# TTFT_LIS2DS12.net
KiCad netlist of a schematic drawn in Altium Designer
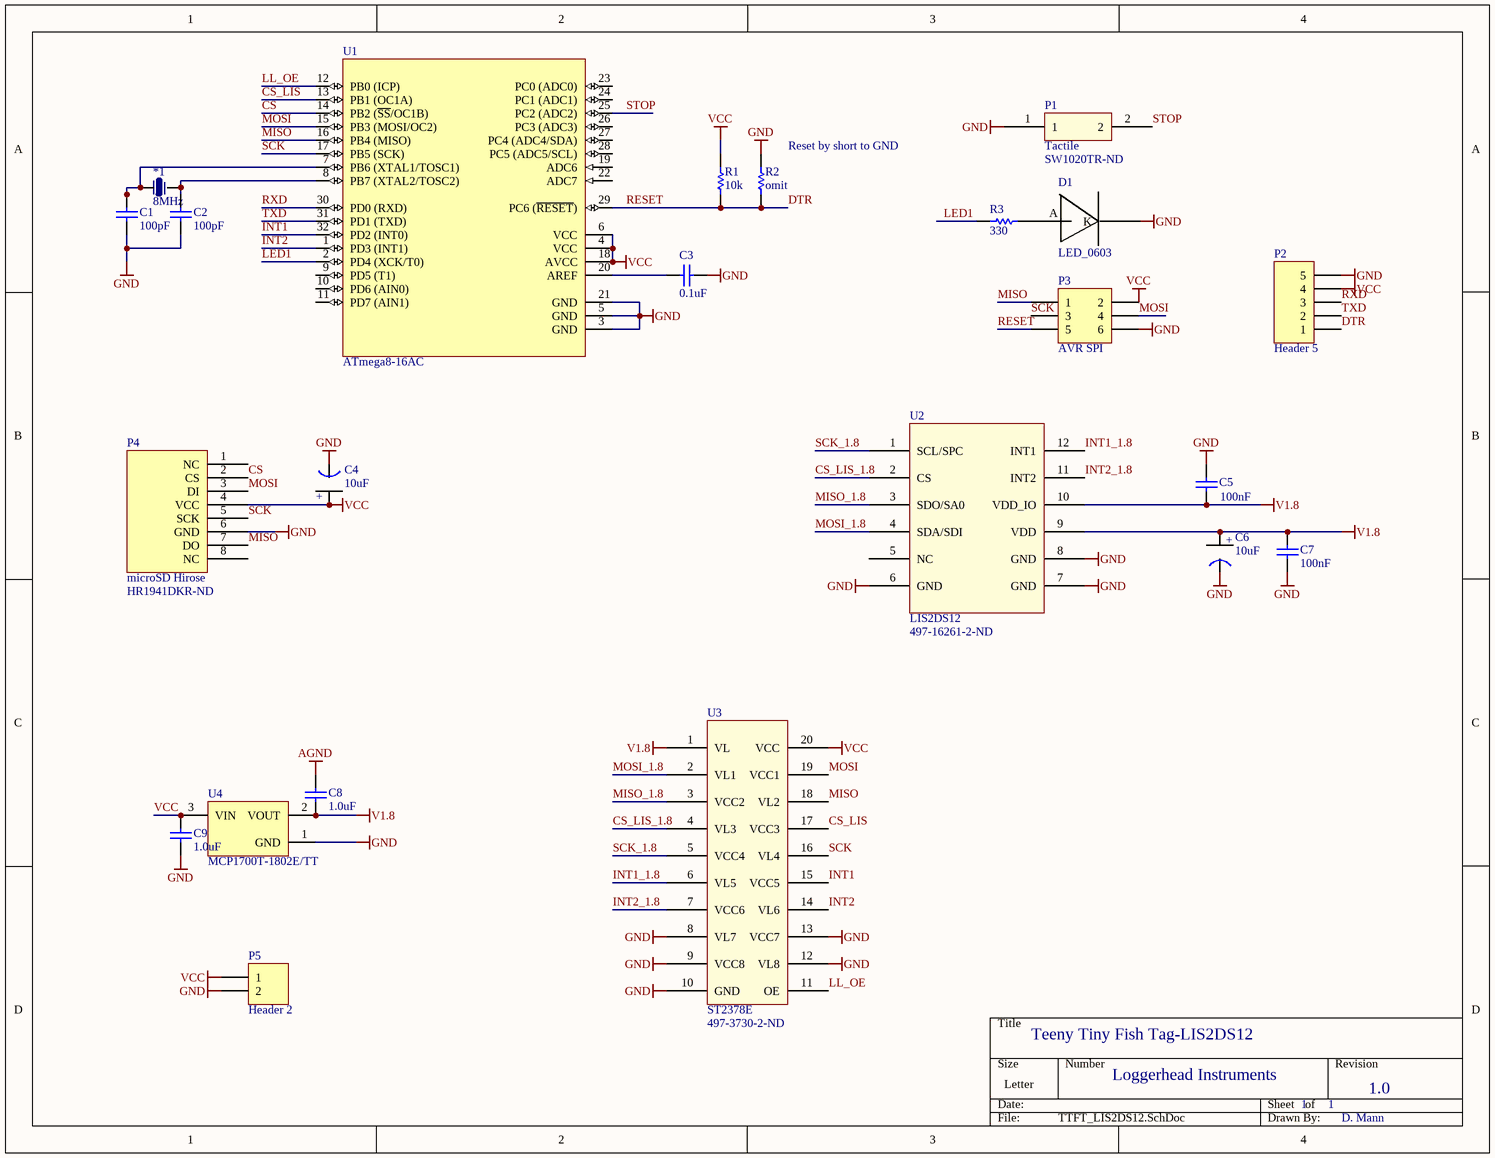
[diagram p0: TTFT_LIS2DS12.SchDoc]

(export (version "E")
  (design (tool "Eeschema 10.0.6"))
  (components
    (comp (ref "*1") (value "8MHz") (footprint "XTAL-ABM3") (libsource (lib "Loggerhead") (part "XTAL-ABM3")))
    (comp (ref "C1")
      (value "100pF")
      (footprint "0402")
      (description "Ceramic Chip Capacitor - Standard")
      (fields (field (name "PUBLISHER") "Altium Limited"))
      (libsource (lib "KEMET Chip Capacitor") (part "C0402"))
    )
    (comp (ref "C2")
      (value "100pF")
      (footprint "0402")
      (description "Ceramic Chip Capacitor - Standard")
      (fields (field (name "PUBLISHER") "Altium Limited"))
      (libsource (lib "KEMET Chip Capacitor") (part "C0402"))
    )
    (comp (ref "C3")
      (value "0.1uF")
      (footprint "0402")
      (description "Ceramic Chip Capacitor - Standard")
      (fields (field (name "PUBLISHER") "Altium Limited"))
      (libsource (lib "KEMET Chip Capacitor") (part "C0402"))
    )
    (comp (ref "C4") (value "10uF") (footprint "Tant0805") (libsource (lib "Loggerhead") (part "Tant0805")))
    (comp (ref "C5")
      (value "100nF")
      (footprint "0402")
      (description "Ceramic Chip Capacitor - Standard")
      (fields (field (name "PUBLISHER") "Altium Limited"))
      (libsource (lib "KEMET Chip Capacitor") (part "C0402"))
    )
    (comp (ref "C6") (value "10uF") (footprint "Tant0805") (libsource (lib "Loggerhead") (part "Tant0805")))
    (comp (ref "C7")
      (value "100nF")
      (footprint "0402")
      (description "Ceramic Chip Capacitor - Standard")
      (fields (field (name "PUBLISHER") "Altium Limited"))
      (libsource (lib "KEMET Chip Capacitor") (part "C0402"))
    )
    (comp (ref "C8")
      (value "1.0uF")
      (footprint "0402")
      (description "Ceramic Chip Capacitor - Standard")
      (fields (field (name "PUBLISHER") "Altium Limited"))
      (libsource (lib "KEMET Chip Capacitor") (part "C0402"))
    )
    (comp (ref "C9")
      (value "1.0uF")
      (footprint "0402")
      (description "Ceramic Chip Capacitor - Standard")
      (fields (field (name "PUBLISHER") "Altium Limited"))
      (libsource (lib "KEMET Chip Capacitor") (part "C0402"))
    )
    (comp (ref "D1")
      (value "LED_0603")
      (footprint "Diode0603")
      (libsource (lib "Loggerhead") (part "LED_0603"))
    )
    (comp (ref "P1")
      (value "Tactile")
      (footprint "Tactile-B3U-1000")
      (fields (field (name "SUPPLIER PART NUMBER 1") "SW1020TR-ND"))
      (libsource (lib "Loggerhead") (part "Tactile_B3U-1000"))
    )
    (comp (ref "P2")
      (value "Header 5")
      (footprint "HDR1X5")
      (description "Header, 5-Pin")
      (fields (field (name "PUBLISHER") "Altium Limited"))
      (libsource (lib "Miscellaneous Connectors") (part "Header 5"))
    )
    (comp (ref "P3")
      (value "AVR SPI")
      (footprint "HDR2X3")
      (description "Header, 3-Pin, Dual row")
      (fields (field (name "PUBLISHER") "Altium Limited"))
      (libsource (lib "Miscellaneous Connectors") (part "Header 3X2"))
    )
    (comp (ref "P4")
      (value "microSD Hirose")
      (footprint "DM3D microSD")
      (fields (field (name "SUPPLIER PART NUMBER 1") "HR1941DKR-ND"))
      (libsource (lib "Loggerhead") (part "microSD Hirose"))
    )
    (comp (ref "P5")
      (value "Header 2")
      (footprint "HDR1X2")
      (description "Header, 2-Pin")
      (fields (field (name "PUBLISHER") "Altium Limited"))
      (libsource (lib "Miscellaneous Connectors") (part "Header 2"))
    )
    (comp (ref "R1")
      (value "10k")
      (footprint "3-0603")
      (fields (field (name "PUBLISHER") "Altium Limited"))
      (libsource (lib "Panasonic Resistor") (part "ERJ3RK"))
    )
    (comp (ref "R2")
      (value "omit")
      (footprint "3-0603")
      (fields (field (name "PUBLISHER") "Altium Limited"))
      (libsource (lib "Panasonic Resistor") (part "ERJ3RK"))
    )
    (comp (ref "R3")
      (value "330")
      (footprint "3-0603")
      (fields (field (name "PUBLISHER") "Altium Limited"))
      (libsource (lib "Panasonic Resistor") (part "ERJ3RK"))
    )
    (comp (ref "U1")
      (value "ATmega8-16AC")
      (footprint "32M1-A_M")
      (description "8-Bit AVR Microcontroller with 8K Bytes of In-System Programmable Flash Memory")
      (fields (field (name "PUBLISHER") "Altium Limited"))
      (libsource (lib "Atmel Microcontroller 8-Bit AVR") (part "ATmega8-16AC"))
    )
    (comp (ref "U2")
      (value "LIS2DS12")
      (footprint "LGA-12")
      (fields (field (name "SUPPLIER PART NUMBER 1") "497-16261-2-ND"))
      (libsource (lib "Loggerhead") (part "LIS2DS12"))
    )
    (comp (ref "U3")
      (value "ST2378E")
      (footprint "TSSOP20")
      (fields (field (name "SUPPLIER PART NUMBER 1") "497-3730-2-ND"))
      (libsource (lib "Loggerhead") (part "ST2378E"))
    )
    (comp (ref "U4")
      (value "MCP1700T-1802E/TT")
      (footprint "SOT-23-TT3_N")
      (description "Low Quiescent Current LDO, 3-Pin SOT-23, Extended Temperature, Tape and Reel")
      (fields (field (name "MANUFACTURER") "Microchip"))
      (libsource (lib "Microchip Power Management Line Regulator") (part "MCP1700T-1802E/TT"))
    )
  )
  (nets
    (net (code "1") (name "/CS") (class "Default")
      (node (ref "P4") (pin "2") (pinfunction "CS_2") (pintype "passive"))
      (node (ref "U1") (pin "14") (pinfunction "PB2_(~{SS}/OC1B)_14") (pintype "bidirectional"))
    )
    (net (code "2") (name "/CS_LIS") (class "Default")
      (node (ref "U1") (pin "13") (pinfunction "PB1_(OC1A)_13") (pintype "bidirectional"))
      (node (ref "U3") (pin "17") (pinfunction "VCC3_17") (pintype "passive"))
    )
    (net (code "3") (name "/CS_LIS_1.8") (class "Default")
      (node (ref "U2") (pin "2") (pinfunction "CS_2") (pintype "passive"))
      (node (ref "U3") (pin "4") (pinfunction "VL3_4") (pintype "passive"))
    )
    (net (code "4") (name "/DTR") (class "Default")
      (node (ref "P2") (pin "1") (pinfunction "1_1") (pintype "passive"))
      (node (ref "P3") (pin "5") (pinfunction "5_5") (pintype "passive"))
      (node (ref "R1") (pin "1") (pinfunction "1_1") (pintype "passive"))
      (node (ref "R2") (pin "1") (pinfunction "1_1") (pintype "passive"))
      (node (ref "U1") (pin "29") (pinfunction "PC6_(~{RESET})_29") (pintype "bidirectional"))
    )
    (net (code "5") (name "/INT1") (class "Default")
      (node (ref "U1") (pin "32") (pinfunction "PD2_(INT0)_32") (pintype "bidirectional"))
      (node (ref "U3") (pin "15") (pinfunction "VCC5_15") (pintype "passive"))
    )
    (net (code "6") (name "/INT1_1.8") (class "Default")
      (node (ref "U2") (pin "12") (pinfunction "INT1_12") (pintype "passive"))
      (node (ref "U3") (pin "6") (pinfunction "VL5_6") (pintype "passive"))
    )
    (net (code "7") (name "/INT2") (class "Default")
      (node (ref "U1") (pin "1") (pinfunction "PD3_(INT1)_1") (pintype "bidirectional"))
      (node (ref "U3") (pin "14") (pinfunction "VL6_14") (pintype "passive"))
    )
    (net (code "8") (name "/INT2_1.8") (class "Default")
      (node (ref "U2") (pin "11") (pinfunction "INT2_11") (pintype "passive"))
      (node (ref "U3") (pin "7") (pinfunction "VCC6_7") (pintype "passive"))
    )
    (net (code "9") (name "/LED1") (class "Default")
      (node (ref "R3") (pin "1") (pinfunction "1_1") (pintype "passive"))
      (node (ref "U1") (pin "2") (pinfunction "PD4_(XCK/T0)_2") (pintype "bidirectional"))
    )
    (net (code "10") (name "/LL_OE") (class "Default")
      (node (ref "U1") (pin "12") (pinfunction "PB0_(ICP)_12") (pintype "bidirectional"))
      (node (ref "U3") (pin "11") (pinfunction "OE_11") (pintype "passive"))
    )
    (net (code "11") (name "/MISO") (class "Default")
      (node (ref "P3") (pin "1") (pinfunction "1_1") (pintype "passive"))
      (node (ref "P4") (pin "7") (pinfunction "DO_7") (pintype "passive"))
      (node (ref "U1") (pin "16") (pinfunction "PB4_(MISO)_16") (pintype "bidirectional"))
      (node (ref "U3") (pin "18") (pinfunction "VL2_18") (pintype "passive"))
    )
    (net (code "12") (name "/MISO_1.8") (class "Default")
      (node (ref "U2") (pin "3") (pinfunction "SDO/SA0_3") (pintype "passive"))
      (node (ref "U3") (pin "3") (pinfunction "VCC2_3") (pintype "passive"))
    )
    (net (code "13") (name "/MOSI") (class "Default")
      (node (ref "P3") (pin "4") (pinfunction "4_4") (pintype "passive"))
      (node (ref "P4") (pin "3") (pinfunction "DI_3") (pintype "passive"))
      (node (ref "U1") (pin "15") (pinfunction "PB3_(MOSI/OC2)_15") (pintype "bidirectional"))
      (node (ref "U3") (pin "19") (pinfunction "VCC1_19") (pintype "passive"))
    )
    (net (code "14") (name "/MOSI_1.8") (class "Default")
      (node (ref "U2") (pin "4") (pinfunction "SDA/SDI_4") (pintype "passive"))
      (node (ref "U3") (pin "2") (pinfunction "VL1_2") (pintype "passive"))
    )
    (net (code "15") (name "/RXD") (class "Default")
      (node (ref "P2") (pin "3") (pinfunction "3_3") (pintype "passive"))
      (node (ref "U1") (pin "30") (pinfunction "PD0_(RXD)_30") (pintype "bidirectional"))
    )
    (net (code "16") (name "/SCK") (class "Default")
      (node (ref "P3") (pin "3") (pinfunction "3_3") (pintype "passive"))
      (node (ref "P4") (pin "5") (pinfunction "SCK_5") (pintype "passive"))
      (node (ref "U1") (pin "17") (pinfunction "PB5_(SCK)_17") (pintype "bidirectional"))
      (node (ref "U3") (pin "16") (pinfunction "VL4_16") (pintype "passive"))
    )
    (net (code "17") (name "/SCK_1.8") (class "Default")
      (node (ref "U2") (pin "1") (pinfunction "SCL/SPC_1") (pintype "passive"))
      (node (ref "U3") (pin "5") (pinfunction "VCC4_5") (pintype "passive"))
    )
    (net (code "18") (name "/STOP") (class "Default")
      (node (ref "P1") (pin "2") (pinfunction "2_2") (pintype "passive"))
      (node (ref "U1") (pin "25") (pinfunction "PC2_(ADC2)_25") (pintype "bidirectional"))
    )
    (net (code "19") (name "/TXD") (class "Default")
      (node (ref "P2") (pin "2") (pinfunction "2_2") (pintype "passive"))
      (node (ref "U1") (pin "31") (pinfunction "PD1_(TXD)_31") (pintype "bidirectional"))
    )
    (net (code "20") (name "AGND") (class "Default")
      (node (ref "C8") (pin "2") (pinfunction "2_2") (pintype "passive"))
    )
    (net (code "21") (name "GND") (class "Default")
      (node (ref "C1") (pin "1") (pinfunction "1_1") (pintype "passive"))
      (node (ref "C2") (pin "1") (pinfunction "1_1") (pintype "passive"))
      (node (ref "C3") (pin "2") (pinfunction "2_2") (pintype "passive"))
      (node (ref "C4") (pin "1") (pinfunction "GND_1") (pintype "passive"))
      (node (ref "C5") (pin "2") (pinfunction "2_2") (pintype "passive"))
      (node (ref "C6") (pin "1") (pinfunction "GND_1") (pintype "passive"))
      (node (ref "C7") (pin "2") (pinfunction "2_2") (pintype "passive"))
      (node (ref "C9") (pin "2") (pinfunction "2_2") (pintype "passive"))
      (node (ref "D1") (pin "K") (pinfunction "K_K") (pintype "passive"))
      (node (ref "P1") (pin "1") (pinfunction "1_1") (pintype "passive"))
      (node (ref "P2") (pin "5") (pinfunction "5_5") (pintype "passive"))
      (node (ref "P3") (pin "6") (pinfunction "6_6") (pintype "passive"))
      (node (ref "P4") (pin "6") (pinfunction "GND_6") (pintype "passive"))
      (node (ref "P5") (pin "2") (pinfunction "2_2") (pintype "passive"))
      (node (ref "R2") (pin "2") (pinfunction "2_2") (pintype "passive"))
      (node (ref "U1") (pin "21") (pinfunction "GND_21") (pintype "power_in"))
      (node (ref "U1") (pin "3") (pinfunction "GND_3") (pintype "power_in"))
      (node (ref "U1") (pin "5") (pinfunction "GND_5") (pintype "power_in"))
      (node (ref "U2") (pin "6") (pinfunction "GND_6") (pintype "passive"))
      (node (ref "U2") (pin "7") (pinfunction "GND_7") (pintype "passive"))
      (node (ref "U2") (pin "8") (pinfunction "GND_8") (pintype "passive"))
      (node (ref "U3") (pin "10") (pinfunction "GND_10") (pintype "passive"))
      (node (ref "U3") (pin "12") (pinfunction "VL8_12") (pintype "passive"))
      (node (ref "U3") (pin "13") (pinfunction "VCC7_13") (pintype "passive"))
      (node (ref "U3") (pin "8") (pinfunction "VL7_8") (pintype "passive"))
      (node (ref "U3") (pin "9") (pinfunction "VCC8_9") (pintype "passive"))
      (node (ref "U4") (pin "1") (pinfunction "GND_1") (pintype "power_in"))
    )
    (net (code "22") (name "Net-(D1-PadA)") (class "Default")
      (node (ref "D1") (pin "A") (pinfunction "A_A") (pintype "passive"))
      (node (ref "R3") (pin "2") (pinfunction "2_2") (pintype "passive"))
    )
    (net (code "23") (name "Net-(U1-AREF)") (class "Default")
      (node (ref "C3") (pin "1") (pinfunction "1_1") (pintype "passive"))
      (node (ref "U1") (pin "20") (pinfunction "AREF_20") (pintype "passive"))
    )
    (net (code "24") (name "Net-(U1-PB6_(XTAL1{slash}TOSC1))") (class "Default")
      (node (ref "*1") (pin "1") (pinfunction "1_1") (pintype "passive"))
      (node (ref "C1") (pin "2") (pinfunction "2_2") (pintype "passive"))
      (node (ref "U1") (pin "7") (pinfunction "PB6_(XTAL1/TOSC1)_7") (pintype "bidirectional"))
    )
    (net (code "25") (name "Net-(U1-PB7_(XTAL2{slash}TOSC2))") (class "Default")
      (node (ref "*1") (pin "2") (pinfunction "2_2") (pintype "passive"))
      (node (ref "C2") (pin "2") (pinfunction "2_2") (pintype "passive"))
      (node (ref "U1") (pin "8") (pinfunction "PB7_(XTAL2/TOSC2)_8") (pintype "bidirectional"))
    )
    (net (code "26") (name "V1.8") (class "Default")
      (node (ref "C5") (pin "1") (pinfunction "1_1") (pintype "passive"))
      (node (ref "C6") (pin "2") (pinfunction "+_2") (pintype "passive"))
      (node (ref "C7") (pin "1") (pinfunction "1_1") (pintype "passive"))
      (node (ref "C8") (pin "1") (pinfunction "1_1") (pintype "passive"))
      (node (ref "U2") (pin "10") (pinfunction "VDD_IO_10") (pintype "passive"))
      (node (ref "U2") (pin "9") (pinfunction "VDD_9") (pintype "passive"))
      (node (ref "U3") (pin "1") (pinfunction "VL_1") (pintype "passive"))
      (node (ref "U4") (pin "2") (pinfunction "VOUT_2") (pintype "power_in"))
    )
    (net (code "27") (name "VCC") (class "Default")
      (node (ref "C4") (pin "2") (pinfunction "+_2") (pintype "passive"))
      (node (ref "C9") (pin "1") (pinfunction "1_1") (pintype "passive"))
      (node (ref "P2") (pin "4") (pinfunction "4_4") (pintype "passive"))
      (node (ref "P3") (pin "2") (pinfunction "2_2") (pintype "passive"))
      (node (ref "P4") (pin "4") (pinfunction "VCC_4") (pintype "passive"))
      (node (ref "P5") (pin "1") (pinfunction "1_1") (pintype "passive"))
      (node (ref "R1") (pin "2") (pinfunction "2_2") (pintype "passive"))
      (node (ref "U1") (pin "18") (pinfunction "AVCC_18") (pintype "power_in"))
      (node (ref "U1") (pin "4") (pinfunction "VCC_4") (pintype "power_in"))
      (node (ref "U1") (pin "6") (pinfunction "VCC_6") (pintype "power_in"))
      (node (ref "U3") (pin "20") (pinfunction "VCC_20") (pintype "passive"))
      (node (ref "U4") (pin "3") (pinfunction "VIN_3") (pintype "power_in"))
    )
    (net (code "28") (name "unconnected-(P4-NC-Pad1)") (class "Default")
      (node (ref "P4") (pin "1") (pinfunction "NC_1") (pintype "passive"))
    )
    (net (code "29") (name "unconnected-(P4-NC-Pad8)") (class "Default")
      (node (ref "P4") (pin "8") (pinfunction "NC_8") (pintype "passive"))
    )
    (net (code "30") (name "unconnected-(U1-ADC6-Pad19)") (class "Default")
      (node (ref "U1") (pin "19") (pinfunction "ADC6_19") (pintype "input"))
    )
    (net (code "31") (name "unconnected-(U1-ADC7-Pad22)") (class "Default")
      (node (ref "U1") (pin "22") (pinfunction "ADC7_22") (pintype "input"))
    )
    (net (code "32") (name "unconnected-(U1-PC0_(ADC0)-Pad23)") (class "Default")
      (node (ref "U1") (pin "23") (pinfunction "PC0_(ADC0)_23") (pintype "bidirectional"))
    )
    (net (code "33") (name "unconnected-(U1-PC1_(ADC1)-Pad24)") (class "Default")
      (node (ref "U1") (pin "24") (pinfunction "PC1_(ADC1)_24") (pintype "bidirectional"))
    )
    (net (code "34") (name "unconnected-(U1-PC3_(ADC3)-Pad26)") (class "Default")
      (node (ref "U1") (pin "26") (pinfunction "PC3_(ADC3)_26") (pintype "bidirectional"))
    )
    (net (code "35") (name "unconnected-(U1-PC4_(ADC4{slash}SDA)-Pad27)") (class "Default")
      (node (ref "U1") (pin "27") (pinfunction "PC4_(ADC4/SDA)_27") (pintype "bidirectional"))
    )
    (net (code "36") (name "unconnected-(U1-PC5_(ADC5{slash}SCL)-Pad28)") (class "Default")
      (node (ref "U1") (pin "28") (pinfunction "PC5_(ADC5/SCL)_28") (pintype "bidirectional"))
    )
    (net (code "37") (name "unconnected-(U1-PD5_(T1)-Pad9)") (class "Default")
      (node (ref "U1") (pin "9") (pinfunction "PD5_(T1)_9") (pintype "bidirectional"))
    )
    (net (code "38") (name "unconnected-(U1-PD6_(AIN0)-Pad10)") (class "Default")
      (node (ref "U1") (pin "10") (pinfunction "PD6_(AIN0)_10") (pintype "bidirectional"))
    )
    (net (code "39") (name "unconnected-(U1-PD7_(AIN1)-Pad11)") (class "Default")
      (node (ref "U1") (pin "11") (pinfunction "PD7_(AIN1)_11") (pintype "bidirectional"))
    )
    (net (code "40") (name "unconnected-(U2-NC-Pad5)") (class "Default")
      (node (ref "U2") (pin "5") (pinfunction "NC_5") (pintype "passive"))
    )
  )
)
